# schematG_wny.net
KiCad netlist of a schematic drawn in EAGLE
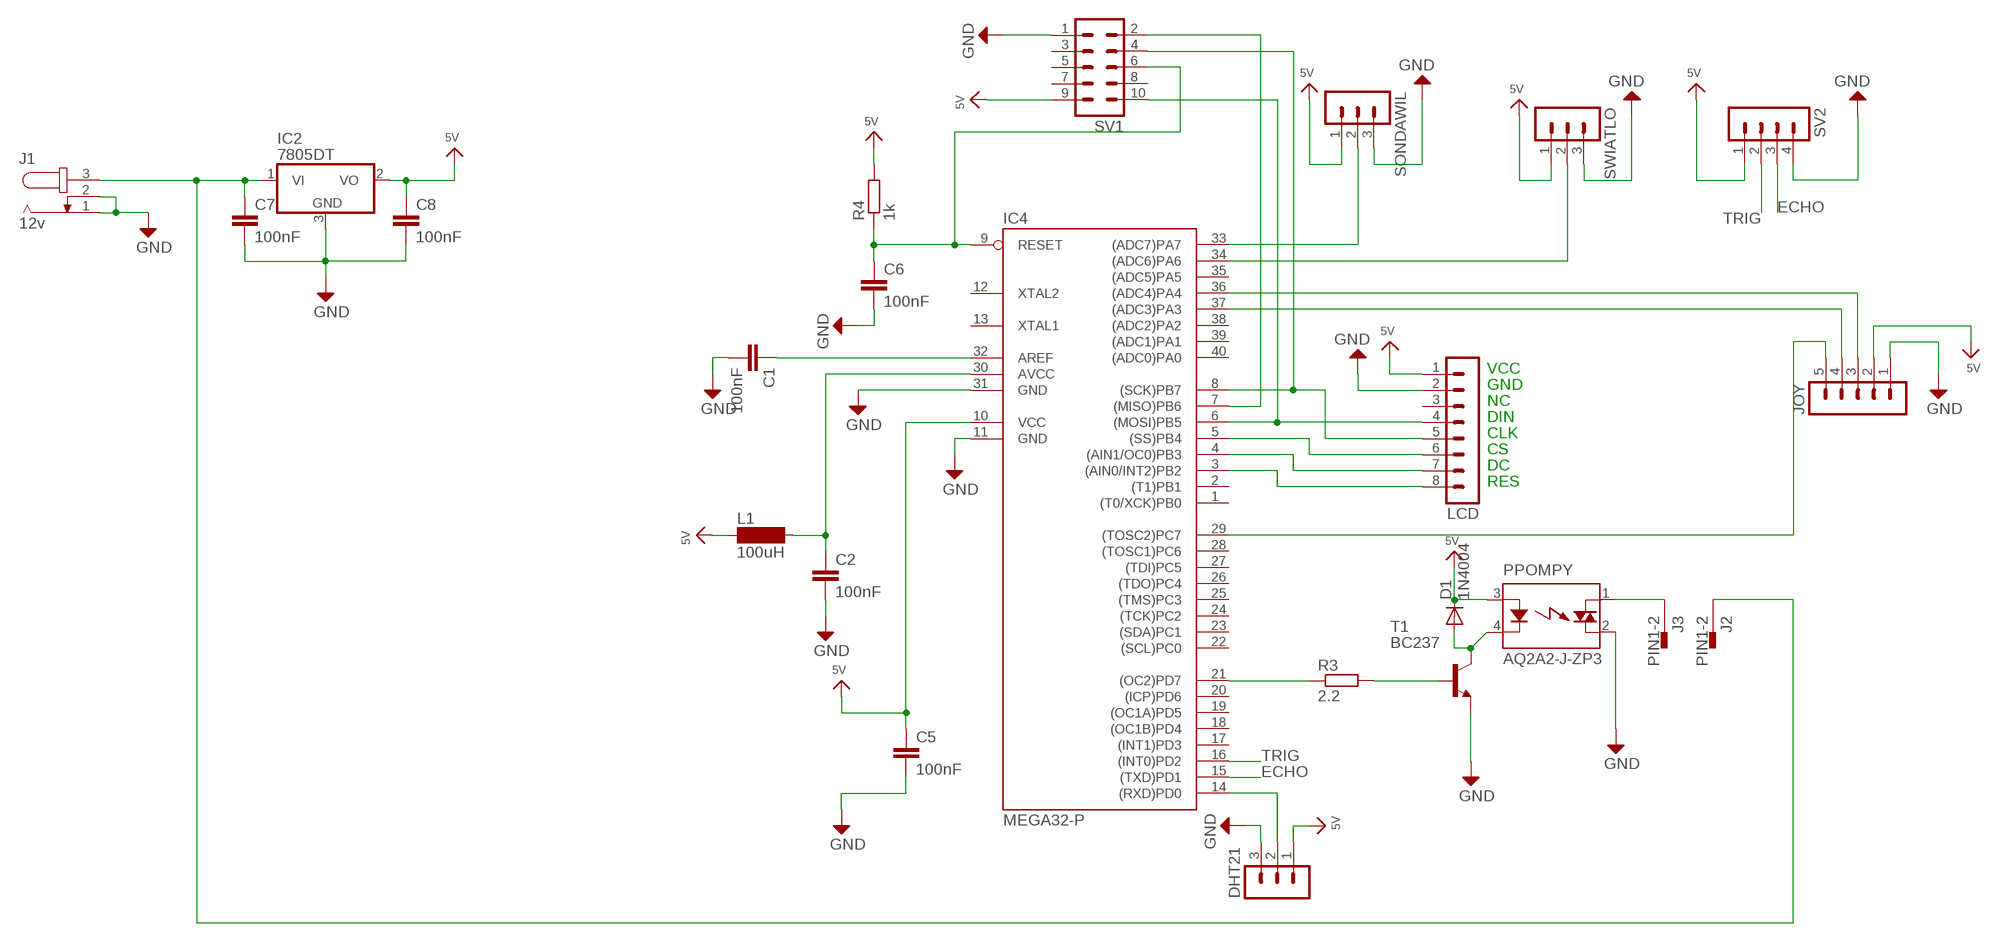
[diagram p0: schematic, sheet 1]

(export (version "E")
  (design (tool "Eeschema 10.0.6"))
  (components
    (comp (ref "C1")
      (value "100nF")
      (footprint "eagle-import:C2.5-6")
      (libsource (lib "eagle-import") (part "C2.5/6"))
    )
    (comp (ref "C2")
      (value "100nF")
      (footprint "eagle-import:C2.5-6")
      (libsource (lib "eagle-import") (part "C2.5/6"))
    )
    (comp (ref "C5")
      (value "100nF")
      (footprint "eagle-import:C2.5-6")
      (libsource (lib "eagle-import") (part "C2.5/6"))
    )
    (comp (ref "C6")
      (value "100nF")
      (footprint "eagle-import:C2.5-6")
      (libsource (lib "eagle-import") (part "C2.5/6"))
    )
    (comp (ref "C7")
      (value "100nF")
      (footprint "eagle-import:C2.5-6")
      (libsource (lib "eagle-import") (part "C2.5/6"))
    )
    (comp (ref "C8")
      (value "100nF")
      (footprint "eagle-import:C2.5-6")
      (libsource (lib "eagle-import") (part "C2.5/6"))
    )
    (comp (ref "D1")
      (value "1N4004")
      (footprint "eagle-import:DO41-10")
      (libsource (lib "eagle-import") (part "1N4004"))
    )
    (comp (ref "DHT21")
      (value "MA03-1")
      (footprint "eagle-import:MA03-1")
      (libsource (lib "eagle-import") (part "MA03-1"))
    )
    (comp (ref "IC2")
      (value "7805DT")
      (footprint "eagle-import:TO252")
      (libsource (lib "eagle-import") (part "78DT05"))
    )
    (comp (ref "IC4")
      (value "MEGA32-P")
      (footprint "eagle-import:DIL40")
      (fields (field (name "MPN") "ATMEGA32-16PU"))
      (libsource (lib "eagle-import") (part "MEGA32-P"))
    )
    (comp (ref "J1")
      (value "12v")
      (footprint "eagle-import:SPC4078")
      (libsource (lib "eagle-import") (part "JACK-PLUG1"))
    )
    (comp (ref "J2")
      (value "PIN1-2")
      (footprint "eagle-import:62221")
      (fields (field (name "MF") "TYCO ELECTRONICS") (field (name "MPN") "62221-1"))
      (libsource (lib "eagle-import") (part "PIN1-2"))
    )
    (comp (ref "J3")
      (value "PIN1-2")
      (footprint "eagle-import:62221")
      (fields (field (name "MF") "TYCO ELECTRONICS") (field (name "MPN") "62221-1"))
      (libsource (lib "eagle-import") (part "PIN1-2"))
    )
    (comp (ref "JOY")
      (value "MA05-1")
      (footprint "eagle-import:MA05-1")
      (libsource (lib "eagle-import") (part "MA05-1"))
    )
    (comp (ref "L1")
      (value "100uH")
      (footprint "eagle-import:BS75")
      (libsource (lib "eagle-import") (part "BS75"))
    )
    (comp (ref "LCD")
      (value "MA08-1")
      (footprint "eagle-import:MA08-1")
      (libsource (lib "eagle-import") (part "MA08-1"))
    )
    (comp (ref "PPOMPY")
      (value "AQ2A2-J-ZP3")
      (footprint "eagle-import:AQ1-FLAT")
      (fields (field (name "MPN") "AQ2A2-ZP3/28VDC"))
      (libsource (lib "eagle-import") (part "AQ?2A2-J-ZP3"))
    )
    (comp (ref "R3")
      (value "2.2")
      (footprint "eagle-import:0207_15")
      (libsource (lib "eagle-import") (part "R-EU_0207/15"))
    )
    (comp (ref "R4")
      (value "1k")
      (footprint "eagle-import:0207_15")
      (libsource (lib "eagle-import") (part "R-EU_0207/15"))
    )
    (comp (ref "SONDAWIL")
      (value "MA03-1")
      (footprint "eagle-import:MA03-1")
      (libsource (lib "eagle-import") (part "MA03-1"))
    )
    (comp (ref "SV1")
      (value "MA05-2")
      (footprint "eagle-import:MA05-2")
      (libsource (lib "eagle-import") (part "MA05-2"))
    )
    (comp (ref "SV2")
      (value "MA04-1")
      (footprint "eagle-import:MA04-1")
      (libsource (lib "eagle-import") (part "MA04-1"))
    )
    (comp (ref "SWIATLO")
      (value "MA03-1")
      (footprint "eagle-import:MA03-1")
      (libsource (lib "eagle-import") (part "MA03-1"))
    )
    (comp (ref "T1")
      (value "BC237")
      (footprint "eagle-import:TO92")
      (libsource (lib "eagle-import") (part "BC237"))
    )
  )
  (nets
    (net (code "1") (name "/ECHO") (class "Default")
      (node (ref "IC4") (pin "15") (pinfunction "(TXD)PD1_15") (pintype "bidirectional"))
      (node (ref "SV2") (pin "3") (pinfunction "3_3") (pintype "passive"))
    )
    (net (code "2") (name "/TRIG") (class "Default")
      (node (ref "IC4") (pin "16") (pinfunction "(INT0)PD2_16") (pintype "bidirectional"))
      (node (ref "SV2") (pin "2") (pinfunction "2_2") (pintype "passive"))
    )
    (net (code "3") (name "5V") (class "Default")
      (node (ref "C5") (pin "1") (pinfunction "1_1") (pintype "passive"))
      (node (ref "C8") (pin "1") (pinfunction "1_1") (pintype "passive"))
      (node (ref "D1") (pin "C") (pinfunction "C_C") (pintype "passive"))
      (node (ref "DHT21") (pin "1") (pinfunction "1_1") (pintype "passive"))
      (node (ref "IC2") (pin "2") (pinfunction "VO_2") (pintype "passive"))
      (node (ref "IC4") (pin "10") (pinfunction "VCC_10") (pintype "power_in"))
      (node (ref "JOY") (pin "2") (pinfunction "2_2") (pintype "passive"))
      (node (ref "L1") (pin "1") (pinfunction "1_1") (pintype "passive"))
      (node (ref "LCD") (pin "1") (pinfunction "1_1") (pintype "passive"))
      (node (ref "PPOMPY") (pin "3") (pinfunction "A_3") (pintype "passive"))
      (node (ref "R4") (pin "2") (pinfunction "2_2") (pintype "passive"))
      (node (ref "SONDAWIL") (pin "1") (pinfunction "1_1") (pintype "passive"))
      (node (ref "SV1") (pin "9") (pinfunction "9_9") (pintype "passive"))
      (node (ref "SV2") (pin "1") (pinfunction "1_1") (pintype "passive"))
      (node (ref "SWIATLO") (pin "1") (pinfunction "1_1") (pintype "passive"))
    )
    (net (code "4") (name "GND") (class "Default")
      (node (ref "C1") (pin "2") (pinfunction "2_2") (pintype "passive"))
      (node (ref "C2") (pin "2") (pinfunction "2_2") (pintype "passive"))
      (node (ref "C5") (pin "2") (pinfunction "2_2") (pintype "passive"))
      (node (ref "C6") (pin "2") (pinfunction "2_2") (pintype "passive"))
      (node (ref "C7") (pin "2") (pinfunction "2_2") (pintype "passive"))
      (node (ref "C8") (pin "2") (pinfunction "2_2") (pintype "passive"))
      (node (ref "DHT21") (pin "3") (pinfunction "3_3") (pintype "passive"))
      (node (ref "IC2") (pin "3") (pinfunction "GND_3") (pintype "passive"))
      (node (ref "IC4") (pin "11") (pinfunction "GND_11") (pintype "power_in"))
      (node (ref "IC4") (pin "31") (pinfunction "GND_31") (pintype "power_in"))
      (node (ref "J1") (pin "1") (pinfunction "1_1") (pintype "passive"))
      (node (ref "J1") (pin "2") (pinfunction "2_2") (pintype "passive"))
      (node (ref "JOY") (pin "1") (pinfunction "1_1") (pintype "passive"))
      (node (ref "LCD") (pin "2") (pinfunction "2_2") (pintype "passive"))
      (node (ref "PPOMPY") (pin "2") (pinfunction "DS2_2") (pintype "passive"))
      (node (ref "SONDAWIL") (pin "3") (pinfunction "3_3") (pintype "passive"))
      (node (ref "SV1") (pin "1") (pinfunction "1_1") (pintype "passive"))
      (node (ref "SV2") (pin "4") (pinfunction "4_4") (pintype "passive"))
      (node (ref "SWIATLO") (pin "3") (pinfunction "3_3") (pintype "passive"))
      (node (ref "T1") (pin "1") (pinfunction "E_1") (pintype "passive"))
    )
    (net (code "5") (name "Net-(IC2-VI)") (class "Default")
      (node (ref "C7") (pin "1") (pinfunction "1_1") (pintype "passive"))
      (node (ref "IC2") (pin "1") (pinfunction "VI_1") (pintype "input"))
      (node (ref "J1") (pin "3") (pinfunction "3_3") (pintype "passive"))
      (node (ref "J2") (pin "1") (pinfunction "1_1") (pintype "passive"))
    )
    (net (code "6") (name "Net-(IC4-(ADC3)PA3)") (class "Default")
      (node (ref "IC4") (pin "37") (pinfunction "(ADC3)PA3_37") (pintype "bidirectional"))
      (node (ref "JOY") (pin "4") (pinfunction "4_4") (pintype "passive"))
    )
    (net (code "7") (name "Net-(IC4-(ADC4)PA4)") (class "Default")
      (node (ref "IC4") (pin "36") (pinfunction "(ADC4)PA4_36") (pintype "bidirectional"))
      (node (ref "JOY") (pin "3") (pinfunction "3_3") (pintype "passive"))
    )
    (net (code "8") (name "Net-(IC4-(ADC6)PA6)") (class "Default")
      (node (ref "IC4") (pin "34") (pinfunction "(ADC6)PA6_34") (pintype "bidirectional"))
      (node (ref "SWIATLO") (pin "2") (pinfunction "2_2") (pintype "passive"))
    )
    (net (code "9") (name "Net-(IC4-(ADC7)PA7)") (class "Default")
      (node (ref "IC4") (pin "33") (pinfunction "(ADC7)PA7_33") (pintype "bidirectional"))
      (node (ref "SONDAWIL") (pin "2") (pinfunction "2_2") (pintype "passive"))
    )
    (net (code "10") (name "Net-(IC4-(AIN0{slash}INT2)PB2)") (class "Default")
      (node (ref "IC4") (pin "3") (pinfunction "(AIN0/INT2)PB2_3") (pintype "bidirectional"))
      (node (ref "LCD") (pin "8") (pinfunction "8_8") (pintype "passive"))
    )
    (net (code "11") (name "Net-(IC4-(AIN1{slash}OC0)PB3)") (class "Default")
      (node (ref "IC4") (pin "4") (pinfunction "(AIN1/OC0)PB3_4") (pintype "bidirectional"))
      (node (ref "LCD") (pin "7") (pinfunction "7_7") (pintype "passive"))
    )
    (net (code "12") (name "Net-(IC4-(MISO)PB6)") (class "Default")
      (node (ref "IC4") (pin "7") (pinfunction "(MISO)PB6_7") (pintype "bidirectional"))
      (node (ref "SV1") (pin "2") (pinfunction "2_2") (pintype "passive"))
    )
    (net (code "13") (name "Net-(IC4-(MOSI)PB5)") (class "Default")
      (node (ref "IC4") (pin "6") (pinfunction "(MOSI)PB5_6") (pintype "bidirectional"))
      (node (ref "LCD") (pin "4") (pinfunction "4_4") (pintype "passive"))
      (node (ref "SV1") (pin "10") (pinfunction "10_10") (pintype "passive"))
    )
    (net (code "14") (name "Net-(IC4-(OC2)PD7)") (class "Default")
      (node (ref "IC4") (pin "21") (pinfunction "(OC2)PD7_21") (pintype "bidirectional"))
      (node (ref "R3") (pin "1") (pinfunction "1_1") (pintype "passive"))
    )
    (net (code "15") (name "Net-(IC4-(RXD)PD0)") (class "Default")
      (node (ref "DHT21") (pin "2") (pinfunction "2_2") (pintype "passive"))
      (node (ref "IC4") (pin "14") (pinfunction "(RXD)PD0_14") (pintype "bidirectional"))
    )
    (net (code "16") (name "Net-(IC4-(SCK)PB7)") (class "Default")
      (node (ref "IC4") (pin "8") (pinfunction "(SCK)PB7_8") (pintype "bidirectional"))
      (node (ref "LCD") (pin "5") (pinfunction "5_5") (pintype "passive"))
      (node (ref "SV1") (pin "4") (pinfunction "4_4") (pintype "passive"))
    )
    (net (code "17") (name "Net-(IC4-(SS)PB4)") (class "Default")
      (node (ref "IC4") (pin "5") (pinfunction "(SS)PB4_5") (pintype "bidirectional"))
      (node (ref "LCD") (pin "6") (pinfunction "6_6") (pintype "passive"))
    )
    (net (code "18") (name "Net-(IC4-(TOSC2)PC7)") (class "Default")
      (node (ref "IC4") (pin "29") (pinfunction "(TOSC2)PC7_29") (pintype "bidirectional"))
      (node (ref "JOY") (pin "5") (pinfunction "5_5") (pintype "passive"))
    )
    (net (code "19") (name "Net-(IC4-AREF)") (class "Default")
      (node (ref "C1") (pin "1") (pinfunction "1_1") (pintype "passive"))
      (node (ref "IC4") (pin "32") (pinfunction "AREF_32") (pintype "passive"))
    )
    (net (code "20") (name "Net-(IC4-AVCC)") (class "Default")
      (node (ref "C2") (pin "1") (pinfunction "1_1") (pintype "passive"))
      (node (ref "IC4") (pin "30") (pinfunction "AVCC_30") (pintype "power_in"))
      (node (ref "L1") (pin "2") (pinfunction "2_2") (pintype "passive"))
    )
    (net (code "21") (name "Net-(IC4-RESET)") (class "Default")
      (node (ref "C6") (pin "1") (pinfunction "1_1") (pintype "passive"))
      (node (ref "IC4") (pin "9") (pinfunction "RESET_9") (pintype "input"))
      (node (ref "R4") (pin "1") (pinfunction "1_1") (pintype "passive"))
      (node (ref "SV1") (pin "6") (pinfunction "6_6") (pintype "passive"))
    )
    (net (code "22") (name "Net-(PPOMPY-DS1)") (class "Default")
      (node (ref "J3") (pin "1") (pinfunction "1_1") (pintype "passive"))
      (node (ref "PPOMPY") (pin "1") (pinfunction "DS1_1") (pintype "passive"))
    )
    (net (code "23") (name "Net-(PPOMPY-K)") (class "Default")
      (node (ref "D1") (pin "A") (pinfunction "A_A") (pintype "passive"))
      (node (ref "PPOMPY") (pin "4") (pinfunction "K_4") (pintype "passive"))
      (node (ref "T1") (pin "3") (pinfunction "C_3") (pintype "passive"))
    )
    (net (code "24") (name "Net-(T1-B)") (class "Default")
      (node (ref "R3") (pin "2") (pinfunction "2_2") (pintype "passive"))
      (node (ref "T1") (pin "2") (pinfunction "B_2") (pintype "passive"))
    )
    (net (code "25") (name "unconnected-(IC4-(ADC0)PA0-Pad40)") (class "Default")
      (node (ref "IC4") (pin "40") (pinfunction "(ADC0)PA0_40") (pintype "bidirectional"))
    )
    (net (code "26") (name "unconnected-(IC4-(ADC1)PA1-Pad39)") (class "Default")
      (node (ref "IC4") (pin "39") (pinfunction "(ADC1)PA1_39") (pintype "bidirectional"))
    )
    (net (code "27") (name "unconnected-(IC4-(ADC2)PA2-Pad38)") (class "Default")
      (node (ref "IC4") (pin "38") (pinfunction "(ADC2)PA2_38") (pintype "bidirectional"))
    )
    (net (code "28") (name "unconnected-(IC4-(ADC5)PA5-Pad35)") (class "Default")
      (node (ref "IC4") (pin "35") (pinfunction "(ADC5)PA5_35") (pintype "bidirectional"))
    )
    (net (code "29") (name "unconnected-(IC4-(ICP)PD6-Pad20)") (class "Default")
      (node (ref "IC4") (pin "20") (pinfunction "(ICP)PD6_20") (pintype "bidirectional"))
    )
    (net (code "30") (name "unconnected-(IC4-(INT1)PD3-Pad17)") (class "Default")
      (node (ref "IC4") (pin "17") (pinfunction "(INT1)PD3_17") (pintype "bidirectional"))
    )
    (net (code "31") (name "unconnected-(IC4-(OC1A)PD5-Pad19)") (class "Default")
      (node (ref "IC4") (pin "19") (pinfunction "(OC1A)PD5_19") (pintype "bidirectional"))
    )
    (net (code "32") (name "unconnected-(IC4-(OC1B)PD4-Pad18)") (class "Default")
      (node (ref "IC4") (pin "18") (pinfunction "(OC1B)PD4_18") (pintype "bidirectional"))
    )
    (net (code "33") (name "unconnected-(IC4-(SCL)PC0-Pad22)") (class "Default")
      (node (ref "IC4") (pin "22") (pinfunction "(SCL)PC0_22") (pintype "bidirectional"))
    )
    (net (code "34") (name "unconnected-(IC4-(SDA)PC1-Pad23)") (class "Default")
      (node (ref "IC4") (pin "23") (pinfunction "(SDA)PC1_23") (pintype "bidirectional"))
    )
    (net (code "35") (name "unconnected-(IC4-(T0{slash}XCK)PB0-Pad1)") (class "Default")
      (node (ref "IC4") (pin "1") (pinfunction "(T0/XCK)PB0_1") (pintype "bidirectional"))
    )
    (net (code "36") (name "unconnected-(IC4-(T1)PB1-Pad2)") (class "Default")
      (node (ref "IC4") (pin "2") (pinfunction "(T1)PB1_2") (pintype "bidirectional"))
    )
    (net (code "37") (name "unconnected-(IC4-(TCK)PC2-Pad24)") (class "Default")
      (node (ref "IC4") (pin "24") (pinfunction "(TCK)PC2_24") (pintype "bidirectional"))
    )
    (net (code "38") (name "unconnected-(IC4-(TDI)PC5-Pad27)") (class "Default")
      (node (ref "IC4") (pin "27") (pinfunction "(TDI)PC5_27") (pintype "bidirectional"))
    )
    (net (code "39") (name "unconnected-(IC4-(TDO)PC4-Pad26)") (class "Default")
      (node (ref "IC4") (pin "26") (pinfunction "(TDO)PC4_26") (pintype "bidirectional"))
    )
    (net (code "40") (name "unconnected-(IC4-(TMS)PC3-Pad25)") (class "Default")
      (node (ref "IC4") (pin "25") (pinfunction "(TMS)PC3_25") (pintype "bidirectional"))
    )
    (net (code "41") (name "unconnected-(IC4-(TOSC1)PC6-Pad28)") (class "Default")
      (node (ref "IC4") (pin "28") (pinfunction "(TOSC1)PC6_28") (pintype "bidirectional"))
    )
    (net (code "42") (name "unconnected-(IC4-XTAL1-Pad13)") (class "Default")
      (node (ref "IC4") (pin "13") (pinfunction "XTAL1_13") (pintype "bidirectional"))
    )
    (net (code "43") (name "unconnected-(IC4-XTAL2-Pad12)") (class "Default")
      (node (ref "IC4") (pin "12") (pinfunction "XTAL2_12") (pintype "bidirectional"))
    )
    (net (code "44") (name "unconnected-(LCD-Pad3)") (class "Default")
      (node (ref "LCD") (pin "3") (pinfunction "3_3") (pintype "passive"))
    )
    (net (code "45") (name "unconnected-(SV1-Pad3)") (class "Default")
      (node (ref "SV1") (pin "3") (pinfunction "3_3") (pintype "passive"))
    )
    (net (code "46") (name "unconnected-(SV1-Pad5)") (class "Default")
      (node (ref "SV1") (pin "5") (pinfunction "5_5") (pintype "passive"))
    )
    (net (code "47") (name "unconnected-(SV1-Pad7)") (class "Default")
      (node (ref "SV1") (pin "7") (pinfunction "7_7") (pintype "passive"))
    )
    (net (code "48") (name "unconnected-(SV1-Pad8)") (class "Default")
      (node (ref "SV1") (pin "8") (pinfunction "8_8") (pintype "passive"))
    )
  )
)
